# schematic2.net
KiCad netlist of a schematic drawn in EAGLE
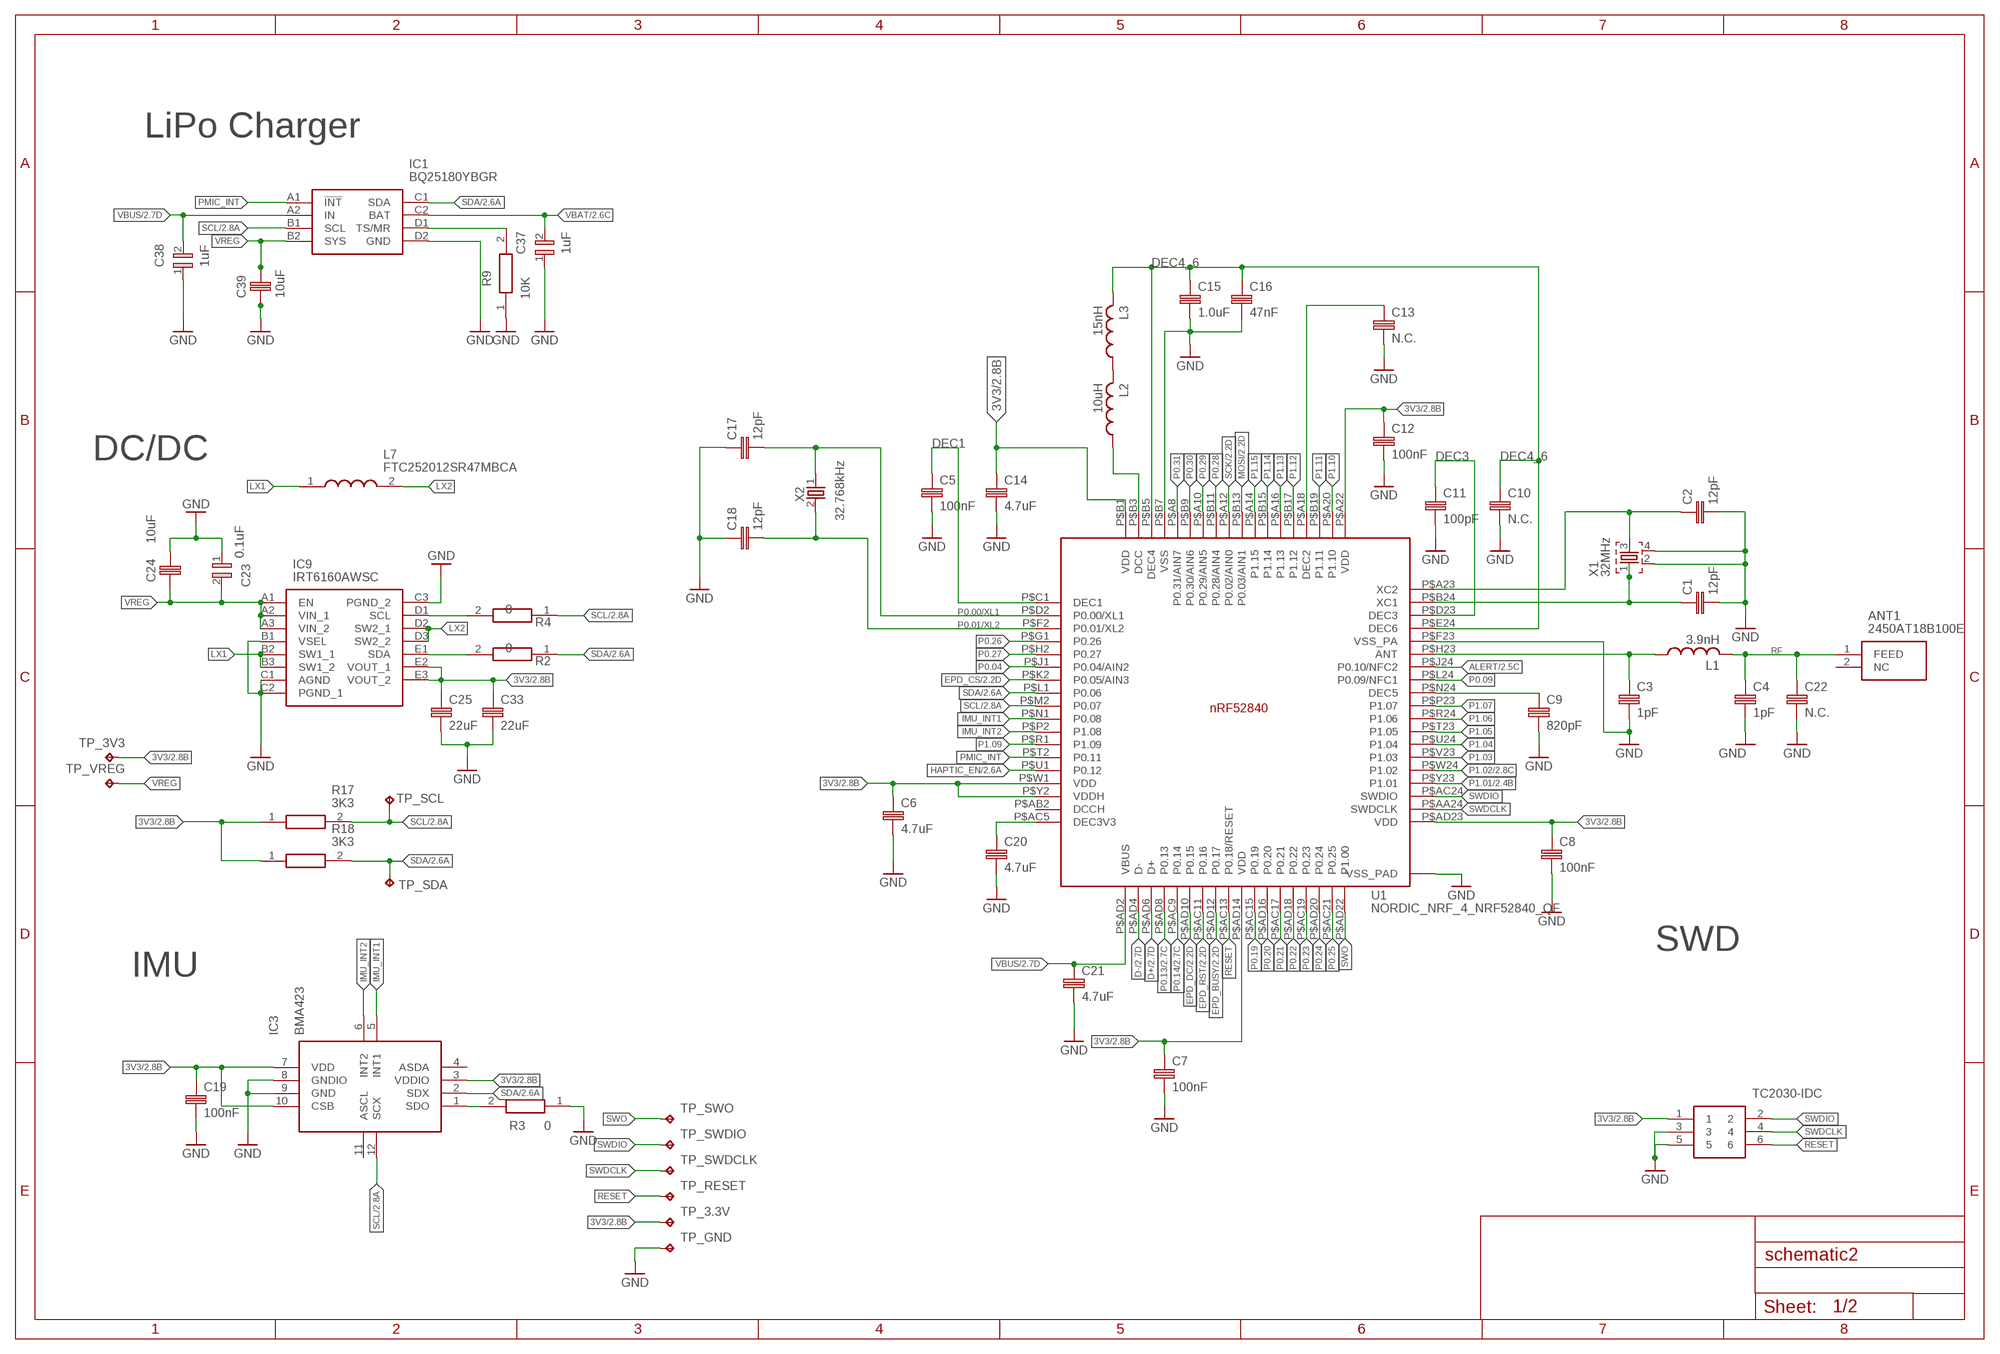
[diagram p0: schematic, sheet 1]
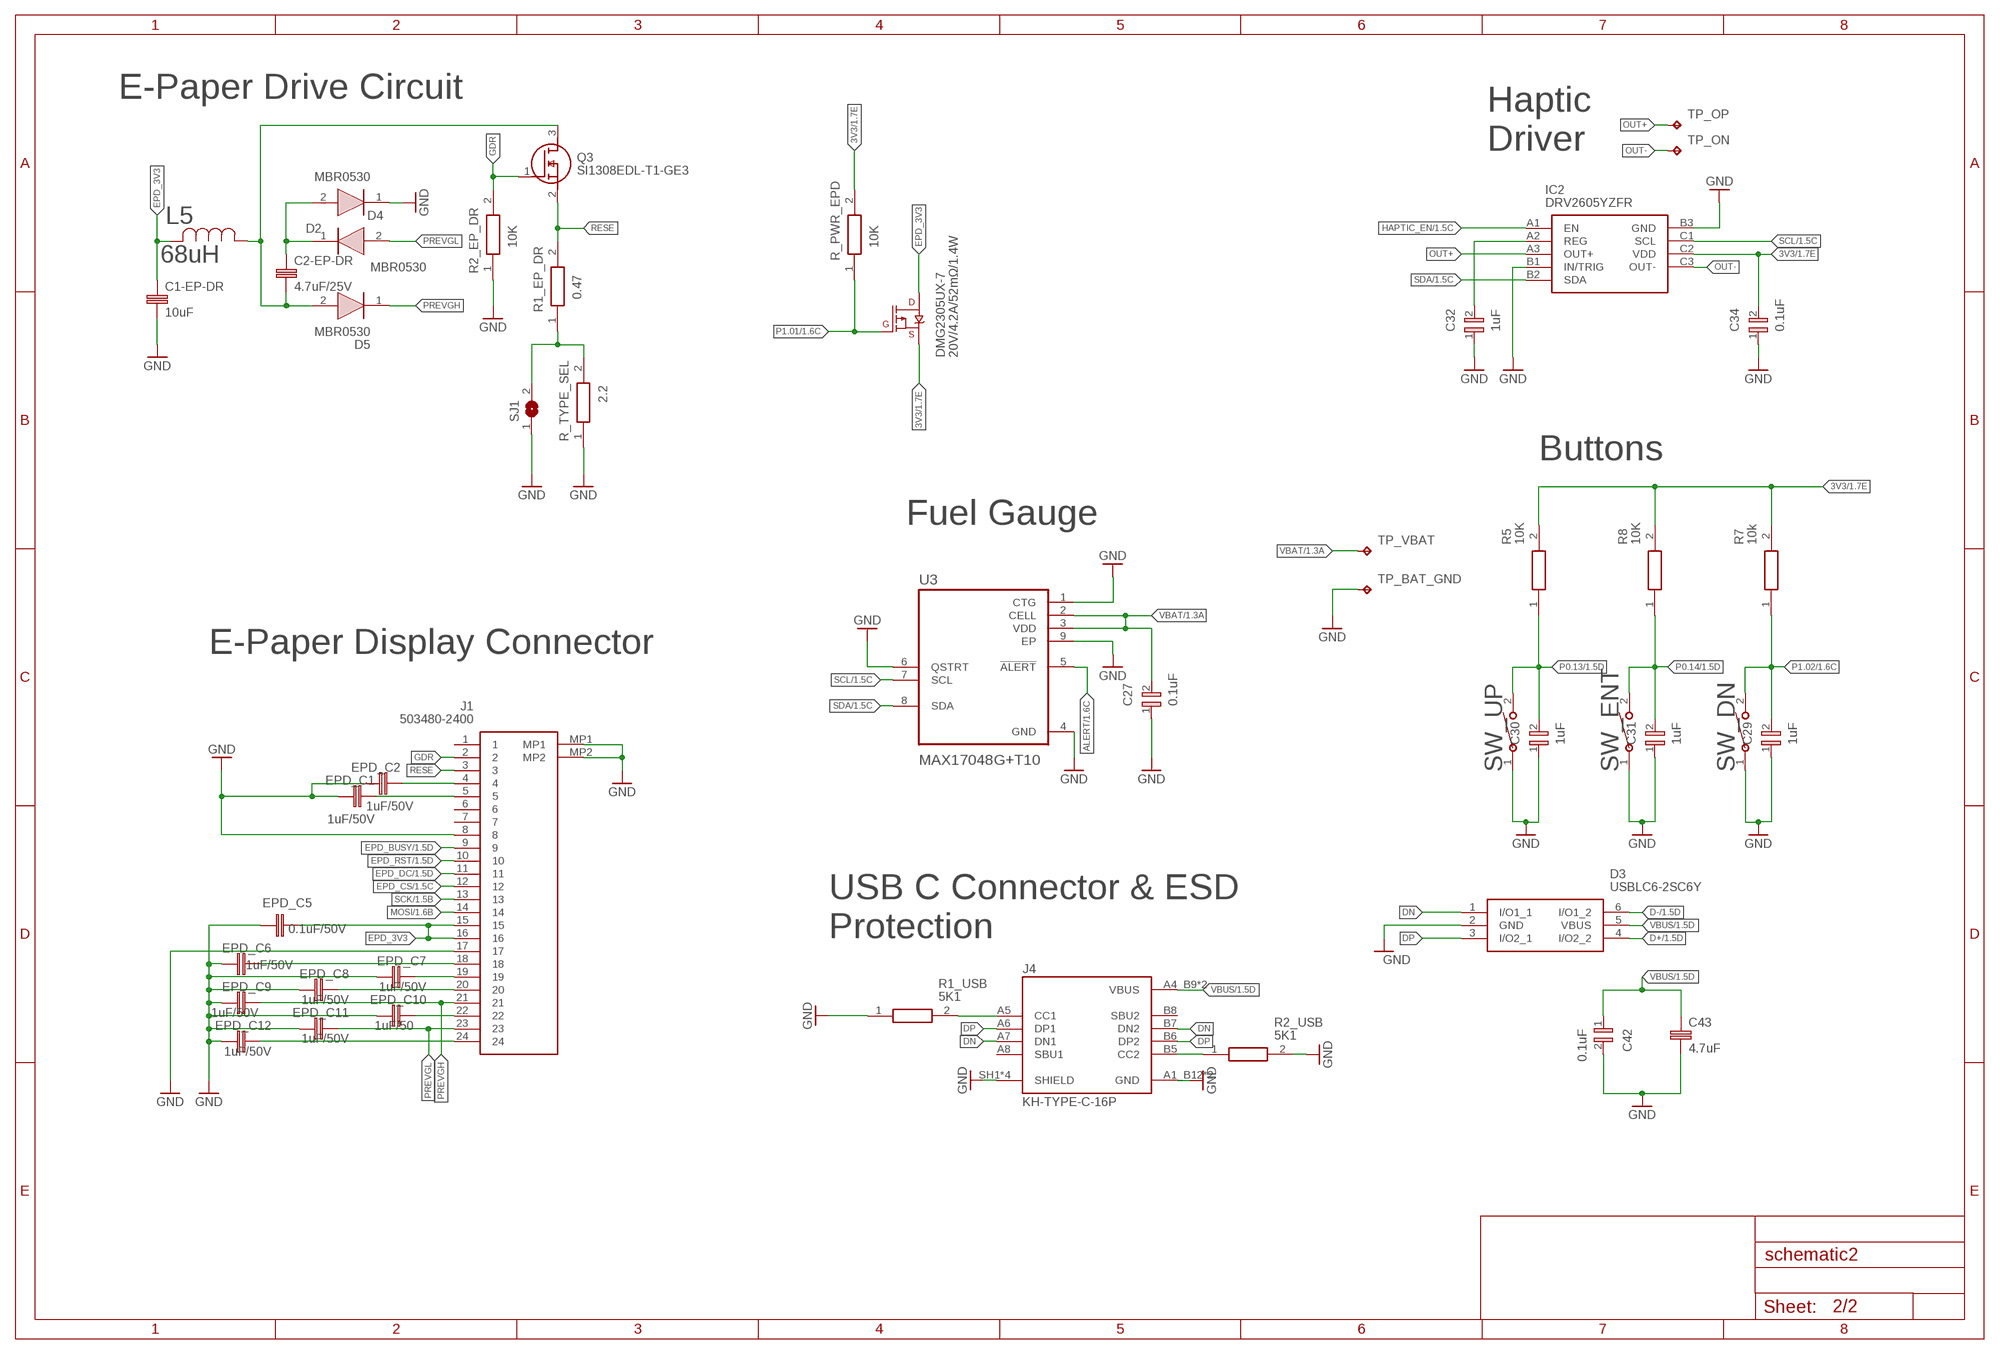
[diagram p1: schematic, sheet 2]

(export (version "E")
  (design (tool "Eeschema 10.0.6"))
  (components
    (comp (ref "ANT1")
      (value "2450AT18B100E")
      (footprint "eagle-import:2450AT18B100E_ANTC3216X140N")
      (fields (field (name "MOUSER_PART_NUMBER") "609-2450AT18B100E"))
      (libsource (lib "eagle-import") (part "2450AT18B100E_2450AT18B100E"))
    )
    (comp (ref "C1")
      (value "12pF")
      (footprint "eagle-import:NORDIC_NRF_3_RESC0201_L")
      (libsource (lib "eagle-import") (part "NORDIC_NRF_3_CAPACITOR_0201_L"))
    )
    (comp (ref "C2")
      (value "12pF")
      (footprint "eagle-import:NORDIC_NRF_3_RESC0201_L")
      (libsource (lib "eagle-import") (part "NORDIC_NRF_3_CAPACITOR_0201_L"))
    )
    (comp (ref "C3")
      (value "1pF")
      (footprint "eagle-import:NORDIC_NRF_3_RESC0201_L")
      (libsource (lib "eagle-import") (part "NORDIC_NRF_3_CAPACITOR_0201_L"))
    )
    (comp (ref "C4")
      (value "1pF")
      (footprint "eagle-import:NORDIC_NRF_3_RESC0201_L")
      (libsource (lib "eagle-import") (part "NORDIC_NRF_3_CAPACITOR_0201_L"))
    )
    (comp (ref "C5")
      (value "100nF")
      (footprint "eagle-import:NORDIC_NRF_3_RESC0201_L")
      (libsource (lib "eagle-import") (part "NORDIC_NRF_3_CAPACITOR_0201_L"))
    )
    (comp (ref "C6")
      (value "4.7uF")
      (footprint "eagle-import:NORDIC_NRF_3_RESC0402_L")
      (libsource (lib "eagle-import") (part "NORDIC_NRF_3_CAPACITOR_0402_L"))
    )
    (comp (ref "C7")
      (value "100nF")
      (footprint "eagle-import:NORDIC_NRF_3_RESC0201_L")
      (libsource (lib "eagle-import") (part "NORDIC_NRF_3_CAPACITOR_0201_L"))
    )
    (comp (ref "C8")
      (value "100nF")
      (footprint "eagle-import:NORDIC_NRF_3_RESC0201_L")
      (libsource (lib "eagle-import") (part "NORDIC_NRF_3_CAPACITOR_0201_L"))
    )
    (comp (ref "C9")
      (value "820pF")
      (footprint "eagle-import:NORDIC_NRF_3_RESC0201_L")
      (libsource (lib "eagle-import") (part "NORDIC_NRF_3_CAPACITOR_0201_L"))
    )
    (comp (ref "C10")
      (value "N.C.")
      (footprint "eagle-import:NORDIC_NRF_3_RESC0201_L")
      (libsource (lib "eagle-import") (part "NORDIC_NRF_3_CAPACITOR_0201_L"))
    )
    (comp (ref "C11")
      (value "100pF")
      (footprint "eagle-import:NORDIC_NRF_3_RESC0201_L")
      (libsource (lib "eagle-import") (part "NORDIC_NRF_3_CAPACITOR_0201_L"))
    )
    (comp (ref "C12")
      (value "100nF")
      (footprint "eagle-import:NORDIC_NRF_3_RESC0201_L")
      (libsource (lib "eagle-import") (part "NORDIC_NRF_3_CAPACITOR_0201_L"))
    )
    (comp (ref "C13")
      (value "N.C.")
      (footprint "eagle-import:NORDIC_NRF_3_RESC0201_L")
      (libsource (lib "eagle-import") (part "NORDIC_NRF_3_CAPACITOR_0201_L"))
    )
    (comp (ref "C14")
      (value "4.7uF")
      (footprint "eagle-import:NORDIC_NRF_3_RESC0402_L")
      (libsource (lib "eagle-import") (part "NORDIC_NRF_3_CAPACITOR_0402_L"))
    )
    (comp (ref "C15")
      (value "1.0uF")
      (footprint "eagle-import:NORDIC_NRF_3_RESC0402_L")
      (libsource (lib "eagle-import") (part "NORDIC_NRF_3_CAPACITOR_0402_L"))
    )
    (comp (ref "C16")
      (value "47nF")
      (footprint "eagle-import:NORDIC_NRF_3_RESC0201_L")
      (libsource (lib "eagle-import") (part "NORDIC_NRF_3_CAPACITOR_0201_L"))
    )
    (comp (ref "C17")
      (value "12pF")
      (footprint "eagle-import:NORDIC_NRF_3_RESC0201_L")
      (libsource (lib "eagle-import") (part "NORDIC_NRF_3_CAPACITOR_0201_L"))
    )
    (comp (ref "C18")
      (value "12pF")
      (footprint "eagle-import:NORDIC_NRF_3_RESC0201_L")
      (libsource (lib "eagle-import") (part "NORDIC_NRF_3_CAPACITOR_0201_L"))
    )
    (comp (ref "C19")
      (value "100nF")
      (footprint "eagle-import:NORDIC_NRF_3_RESC0201_L")
      (libsource (lib "eagle-import") (part "NORDIC_NRF_3_CAPACITOR_0201_L"))
    )
    (comp (ref "C20")
      (value "4.7uF")
      (footprint "eagle-import:NORDIC_NRF_3_RESC0402_L")
      (libsource (lib "eagle-import") (part "NORDIC_NRF_3_CAPACITOR_0402_L"))
    )
    (comp (ref "C21")
      (value "4.7uF")
      (footprint "eagle-import:NORDIC_NRF_3_RESC0402_L")
      (libsource (lib "eagle-import") (part "NORDIC_NRF_3_CAPACITOR_0402_L"))
    )
    (comp (ref "C22")
      (value "N.C.")
      (footprint "eagle-import:NORDIC_NRF_3_RESC0201_L")
      (libsource (lib "eagle-import") (part "NORDIC_NRF_3_CAPACITOR_0201_L"))
    )
    (comp (ref "C23")
      (value "0.1uF")
      (footprint "eagle-import:GRM011R60J152KE01L_2_CAPC0201X13N")
      (fields (field (name "MF") "Murata") (field (name "MP") "GRM011R60J152KE01L"))
      (libsource (lib "eagle-import") (part "GRM011R60J152KE01L_2_GRM011R60J152KE01L"))
    )
    (comp (ref "C24")
      (value "10uF")
      (footprint "eagle-import:NORDIC_NRF_3_RESC0402_L")
      (libsource (lib "eagle-import") (part "NORDIC_NRF_3_CAPACITOR_0402_L"))
    )
    (comp (ref "C25")
      (value "22uF")
      (footprint "eagle-import:NORDIC_NRF_3_RESC0402_L")
      (libsource (lib "eagle-import") (part "NORDIC_NRF_3_CAPACITOR_0402_L"))
    )
    (comp (ref "C33")
      (value "22uF")
      (footprint "eagle-import:NORDIC_NRF_3_RESC0402_L")
      (libsource (lib "eagle-import") (part "NORDIC_NRF_3_CAPACITOR_0402_L"))
    )
    (comp (ref "C37")
      (value "1uF")
      (footprint "eagle-import:GRM011R60J152KE01L_2_CAPC0201X13N")
      (fields (field (name "MF") "Murata") (field (name "MP") "GRM011R60J152KE01L"))
      (libsource (lib "eagle-import") (part "GRM011R60J152KE01L_2_GRM011R60J152KE01L"))
    )
    (comp (ref "C38")
      (value "1uF")
      (footprint "eagle-import:GRM011R60J152KE01L_2_CAPC0201X13N")
      (fields (field (name "MF") "Murata") (field (name "MP") "GRM011R60J152KE01L"))
      (libsource (lib "eagle-import") (part "GRM011R60J152KE01L_2_GRM011R60J152KE01L"))
    )
    (comp (ref "C39")
      (value "10uF")
      (footprint "eagle-import:NORDIC_NRF_3_RESC0402_L")
      (libsource (lib "eagle-import") (part "NORDIC_NRF_3_CAPACITOR_0402_L"))
    )
    (comp (ref "IC1")
      (value "BQ25180YBGR")
      (footprint "eagle-import:BQ25180YBGR_BGA8C40P2X4_100X155X50")
      (fields (field (name "MOUSER_PART_NUMBER") "595-BQ25180YBGR"))
      (libsource (lib "eagle-import") (part "BQ25180YBGR_BQ25180YBGR"))
    )
    (comp (ref "IC3")
      (value "BMA423")
      (footprint "eagle-import:BMA423_BMA423")
      (fields (field (name "MOUSER_PART_NUMBER") "262-BMA423"))
      (libsource (lib "eagle-import") (part "BMA423_BMA423"))
    )
    (comp (ref "IC9")
      (value "IRT6160AWSC")
      (footprint "eagle-import:RT6160AWSC_BGA15C40P3X5_140X230X60")
      (fields
        (field (name "MANUFACTURER_PART_NUMBER") "RT6160AWSC")
        (field (name "MOUSER_PART_NUMBER") "835-RT6160AWSC")
      )
      (libsource (lib "eagle-import") (part "RT6160AWSC_RT6160AWSC"))
    )
    (comp (ref "J2")
      (value "TC2030-IDC")
      (footprint "eagle-import:TC2030-IDC_TC2030IDC")
      (libsource (lib "eagle-import") (part "TC2030-IDC_TC2030-IDC"))
    )
    (comp (ref "L1")
      (value "3.9nH")
      (footprint "eagle-import:NORDIC_NRF_2_RESC0402_L")
      (libsource (lib "eagle-import") (part "NORDIC_NRF_2_INDUCTOR_0402_L"))
    )
    (comp (ref "L2")
      (value "10uH")
      (footprint "eagle-import:NORDIC_NRF_2_RESC0402_L")
      (libsource (lib "eagle-import") (part "NORDIC_NRF_2_INDUCTOR_0402_L"))
    )
    (comp (ref "L3")
      (value "15nH")
      (footprint "eagle-import:NORDIC_NRF_2_RESC0402_L")
      (libsource (lib "eagle-import") (part "NORDIC_NRF_2_INDUCTOR_0402_L"))
    )
    (comp (ref "L7")
      (value "FTC252012SR47MBCA")
      (footprint "eagle-import:MLP2016SR47MT0S1_INDC2016X100N")
      (libsource (lib "eagle-import") (part "MLP2016SR47MT0S1_FTC252012SR47MBCA"))
    )
    (comp (ref "R2")
      (value "0")
      (footprint "eagle-import:ERA-1AEB3401C_0201")
      (libsource (lib "eagle-import") (part "ERA-1AEB3401C_CPF0201D7K68C1"))
    )
    (comp (ref "R3")
      (value "0")
      (footprint "eagle-import:CPF0201D7K68C1_0201")
      (libsource (lib "eagle-import") (part "CPF0201D7K68C1_CPF0201D7K68C1"))
    )
    (comp (ref "R4")
      (value "0")
      (footprint "eagle-import:ERA-1AEB3401C_0201")
      (libsource (lib "eagle-import") (part "ERA-1AEB3401C_CPF0201D7K68C1"))
    )
    (comp (ref "R9")
      (value "10K")
      (footprint "eagle-import:ERA-1AEB3401C_0201")
      (libsource (lib "eagle-import") (part "ERA-1AEB3401C_CPF0201D7K68C1"))
    )
    (comp (ref "R17")
      (value "3K3")
      (footprint "eagle-import:CPF0201D7K68C1_0201")
      (libsource (lib "eagle-import") (part "CPF0201D7K68C1_CPF0201D7K68C1"))
    )
    (comp (ref "R18")
      (value "3K3")
      (footprint "eagle-import:CPF0201D7K68C1_0201")
      (libsource (lib "eagle-import") (part "CPF0201D7K68C1_CPF0201D7K68C1"))
    )
    (comp (ref "TP_3.3V")
      (value "HECTOR_WATCH_1_TPTP20R")
      (footprint "eagle-import:HECTOR_WATCH_1_TP20R")
      (libsource (lib "eagle-import") (part "HECTOR_WATCH_1_TPTP20R"))
    )
    (comp (ref "TP_3V3")
      (value "HECTOR_WATCH_1_TPTP20R")
      (footprint "eagle-import:HECTOR_WATCH_1_TP20R")
      (libsource (lib "eagle-import") (part "HECTOR_WATCH_1_TPTP20R"))
    )
    (comp (ref "TP_GND")
      (value "HECTOR_WATCH_1_TPTP20R")
      (footprint "eagle-import:HECTOR_WATCH_1_TP20R")
      (libsource (lib "eagle-import") (part "HECTOR_WATCH_1_TPTP20R"))
    )
    (comp (ref "TP_RESET")
      (value "HECTOR_WATCH_1_TPTP20R")
      (footprint "eagle-import:HECTOR_WATCH_1_TP20R")
      (libsource (lib "eagle-import") (part "HECTOR_WATCH_1_TPTP20R"))
    )
    (comp (ref "TP_SCL")
      (value "HECTOR_WATCH_1_TPTP20R")
      (footprint "eagle-import:HECTOR_WATCH_1_TP20R")
      (libsource (lib "eagle-import") (part "HECTOR_WATCH_1_TPTP20R"))
    )
    (comp (ref "TP_SDA")
      (value "HECTOR_WATCH_1_TPTP20R")
      (footprint "eagle-import:HECTOR_WATCH_1_TP20R")
      (libsource (lib "eagle-import") (part "HECTOR_WATCH_1_TPTP20R"))
    )
    (comp (ref "TP_SWDCLK")
      (value "HECTOR_WATCH_1_TPTP20R")
      (footprint "eagle-import:HECTOR_WATCH_1_TP20R")
      (libsource (lib "eagle-import") (part "HECTOR_WATCH_1_TPTP20R"))
    )
    (comp (ref "TP_SWDIO")
      (value "HECTOR_WATCH_1_TPTP20R")
      (footprint "eagle-import:HECTOR_WATCH_1_TP20R")
      (libsource (lib "eagle-import") (part "HECTOR_WATCH_1_TPTP20R"))
    )
    (comp (ref "TP_SWO")
      (value "HECTOR_WATCH_1_TPTP20R")
      (footprint "eagle-import:HECTOR_WATCH_1_TP20R")
      (libsource (lib "eagle-import") (part "HECTOR_WATCH_1_TPTP20R"))
    )
    (comp (ref "TP_VREG")
      (value "HECTOR_WATCH_1_TPTP20R")
      (footprint "eagle-import:HECTOR_WATCH_1_TP20R")
      (libsource (lib "eagle-import") (part "HECTOR_WATCH_1_TPTP20R"))
    )
    (comp (ref "U$3")
      (value "NORDIC_NRF_3_CAPACITOR_0402_L")
      (footprint "eagle-import:NORDIC_NRF_3_RESC0402_L")
      (libsource (lib "eagle-import") (part "NORDIC_NRF_3_CAPACITOR_0402_L"))
    )
    (comp (ref "U1")
      (value "NORDIC_NRF_4_NRF52840_QF")
      (footprint "eagle-import:NORDIC_NRF_4_AQFN50P700X700X85_HS-74N")
      (libsource (lib "eagle-import") (part "NORDIC_NRF_4_NRF52840_QF"))
    )
    (comp (ref "X1")
      (value "32MHz")
      (footprint "eagle-import:NORDIC_NRF_BT-XTAL_2016_N")
      (libsource (lib "eagle-import") (part "NORDIC_NRF_XTAL_32MHZ"))
    )
    (comp (ref "X2")
      (value "32.768kHz")
      (footprint "eagle-import:NORDIC_NRF_1_XTAL_3215_N")
      (libsource (lib "eagle-import") (part "NORDIC_NRF_1_XTAL_32KHZ"))
    )
    (comp (ref "C1-EP-DR")
      (value "10uF")
      (footprint "eagle-import:NORDIC_NRF_3_RESC0402_L")
      (libsource (lib "eagle-import") (part "NORDIC_NRF_3_CAPACITOR_0402_L"))
    )
    (comp (ref "C2-EP-DR")
      (value "4.7uF/25V")
      (footprint "eagle-import:NORDIC_NRF_3_RESC0402_L")
      (libsource (lib "eagle-import") (part "NORDIC_NRF_3_CAPACITOR_0402_L"))
    )
    (comp (ref "C27")
      (value "0.1uF")
      (footprint "eagle-import:GRM011R60J152KE01L_2_CAPC0201X13N")
      (fields (field (name "MF") "Murata") (field (name "MP") "GRM011R60J152KE01L"))
      (libsource (lib "eagle-import") (part "GRM011R60J152KE01L_2_GRM011R60J152KE01L"))
    )
    (comp (ref "C29")
      (value "1uF")
      (footprint "eagle-import:GRM011R60J152KE01L_2_CAPC0201X13N")
      (fields (field (name "MF") "Murata") (field (name "MP") "GRM011R60J152KE01L"))
      (libsource (lib "eagle-import") (part "GRM011R60J152KE01L_2_GRM011R60J152KE01L"))
    )
    (comp (ref "C30")
      (value "1uF")
      (footprint "eagle-import:GRM011R60J152KE01L_2_CAPC0201X13N")
      (fields (field (name "MF") "Murata") (field (name "MP") "GRM011R60J152KE01L"))
      (libsource (lib "eagle-import") (part "GRM011R60J152KE01L_2_GRM011R60J152KE01L"))
    )
    (comp (ref "C31")
      (value "1uF")
      (footprint "eagle-import:GRM011R60J152KE01L_2_CAPC0201X13N")
      (fields (field (name "MF") "Murata") (field (name "MP") "GRM011R60J152KE01L"))
      (libsource (lib "eagle-import") (part "GRM011R60J152KE01L_2_GRM011R60J152KE01L"))
    )
    (comp (ref "C32")
      (value "1uF")
      (footprint "eagle-import:GRM011R60J152KE01L_2_CAPC0201X13N")
      (fields (field (name "MF") "Murata") (field (name "MP") "GRM011R60J152KE01L"))
      (libsource (lib "eagle-import") (part "GRM011R60J152KE01L_2_GRM011R60J152KE01L"))
    )
    (comp (ref "C34")
      (value "0.1uF")
      (footprint "eagle-import:GRM011R60J152KE01L_2_CAPC0201X13N")
      (fields (field (name "MF") "Murata") (field (name "MP") "GRM011R60J152KE01L"))
      (libsource (lib "eagle-import") (part "GRM011R60J152KE01L_2_GRM011R60J152KE01L"))
    )
    (comp (ref "C42")
      (value "0.1uF")
      (footprint "eagle-import:GRM011R60J152KE01L_2_CAPC0201X13N")
      (fields (field (name "MF") "Murata") (field (name "MP") "GRM011R60J152KE01L"))
      (libsource (lib "eagle-import") (part "GRM011R60J152KE01L_2_GRM011R60J152KE01L"))
    )
    (comp (ref "C43")
      (value "4.7uF")
      (footprint "eagle-import:NORDIC_NRF_3_RESC0402_L")
      (libsource (lib "eagle-import") (part "NORDIC_NRF_3_CAPACITOR_0402_L"))
    )
    (comp (ref "D2")
      (value "MBR0530")
      (footprint "eagle-import:ESP32_C6_LIBRARY_5_SOD3716X135N")
      (fields (field (name "MF") "ON Semiconductor"))
      (libsource (lib "eagle-import") (part "ESP32_C6_LIBRARY_5_MBR0530"))
    )
    (comp (ref "D3")
      (value "USBLC6-2SC6Y")
      (footprint "eagle-import:ESP32_C6_LIBRARY_3_SOT95P280X145-6N")
      (fields (field (name "MF") "STMicroelectronics"))
      (libsource (lib "eagle-import") (part "ESP32_C6_LIBRARY_3_USBLC6-2SC6Y"))
    )
    (comp (ref "D4")
      (value "MBR0530")
      (footprint "eagle-import:ESP32_C6_LIBRARY_5_SOD3716X135N")
      (fields (field (name "MF") "ON Semiconductor"))
      (libsource (lib "eagle-import") (part "ESP32_C6_LIBRARY_5_MBR0530"))
    )
    (comp (ref "D5")
      (value "MBR0530")
      (footprint "eagle-import:ESP32_C6_LIBRARY_5_SOD3716X135N")
      (fields (field (name "MF") "ON Semiconductor"))
      (libsource (lib "eagle-import") (part "ESP32_C6_LIBRARY_5_MBR0530"))
    )
    (comp (ref "DMG2305UX-7")
      (value "20V/4.2A/52mΩ/1.4W")
      (footprint "eagle-import:ESP32_C6_LIBRARY_4_ESP32_C6_LIBRARY_4_ESP32_C6_LIBRARY_4_ESP32_C6_LIBRARY_4_ESP32_WROVER_SPARKFUN-DISCRETESEMI_SOT23-3")
      (libsource (lib "eagle-import") (part "ESP32_C6_LIBRARY_4_ESP32_WROVER_SPARKFUN-DISCRETESEMI_MOSFET_PCH-DMG2305UX-7"))
    )
    (comp (ref "EPD_C1")
      (value "1uF/50V")
      (footprint "eagle-import:NORDIC_NRF_3_RESC0402_L")
      (libsource (lib "eagle-import") (part "NORDIC_NRF_3_CAPACITOR_0402_L"))
    )
    (comp (ref "EPD_C2")
      (value "1uF/50V")
      (footprint "eagle-import:NORDIC_NRF_3_RESC0402_L")
      (libsource (lib "eagle-import") (part "NORDIC_NRF_3_CAPACITOR_0402_L"))
    )
    (comp (ref "EPD_C5")
      (value "0.1uF/50V")
      (footprint "eagle-import:NORDIC_NRF_3_RESC0201_L")
      (libsource (lib "eagle-import") (part "NORDIC_NRF_3_CAPACITOR_0201_L"))
    )
    (comp (ref "EPD_C6")
      (value "1uF/50V")
      (footprint "eagle-import:NORDIC_NRF_3_RESC0402_L")
      (libsource (lib "eagle-import") (part "NORDIC_NRF_3_CAPACITOR_0402_L"))
    )
    (comp (ref "EPD_C7")
      (value "1uF/50V")
      (footprint "eagle-import:NORDIC_NRF_3_RESC0402_L")
      (libsource (lib "eagle-import") (part "NORDIC_NRF_3_CAPACITOR_0402_L"))
    )
    (comp (ref "EPD_C8")
      (value "1uF/50V")
      (footprint "eagle-import:NORDIC_NRF_3_RESC0402_L")
      (libsource (lib "eagle-import") (part "NORDIC_NRF_3_CAPACITOR_0402_L"))
    )
    (comp (ref "EPD_C9")
      (value "1uF/50V")
      (footprint "eagle-import:NORDIC_NRF_3_RESC0402_L")
      (libsource (lib "eagle-import") (part "NORDIC_NRF_3_CAPACITOR_0402_L"))
    )
    (comp (ref "EPD_C10")
      (value "1uF/50")
      (footprint "eagle-import:NORDIC_NRF_3_RESC0402_L")
      (libsource (lib "eagle-import") (part "NORDIC_NRF_3_CAPACITOR_0402_L"))
    )
    (comp (ref "EPD_C11")
      (value "1uF/50V")
      (footprint "eagle-import:NORDIC_NRF_3_RESC0402_L")
      (libsource (lib "eagle-import") (part "NORDIC_NRF_3_CAPACITOR_0402_L"))
    )
    (comp (ref "EPD_C12")
      (value "1uF/50V")
      (footprint "eagle-import:NORDIC_NRF_3_RESC0402_L")
      (libsource (lib "eagle-import") (part "NORDIC_NRF_3_CAPACITOR_0402_L"))
    )
    (comp (ref "IC2")
      (value "DRV2605YZFR")
      (footprint "eagle-import:DRV2605YZFR_BGA9C50P3X3_144X144X62")
      (libsource (lib "eagle-import") (part "DRV2605YZFR_DRV2605YZFR"))
    )
    (comp (ref "J1")
      (value "503480-2400")
      (footprint "eagle-import:503480-2400_5034802400")
      (fields (field (name "MOUSER_PART_NUMBER") "538-503480-2400"))
      (libsource (lib "eagle-import") (part "503480-2400_503480-2400"))
    )
    (comp (ref "J4")
      (value "KH-TYPE-C-16P")
      (footprint "eagle-import:KH-TYPE-C-16P_KINGHELM_KH-TYPE-C-16P")
      (fields (field (name "MF") "kinghelm"))
      (libsource (lib "eagle-import") (part "KH-TYPE-C-16P_KH-TYPE-C-16P"))
    )
    (comp (ref "L5")
      (value "68uH")
      (footprint "eagle-import:ESP32_C6_LIBRARY_2_IND_4828-WE-TPC_WRE")
      (fields
        (field (name "MANUFACTURER_PART_NUMBER") "744043680")
        (field (name "COPYRIGHT") "Copyright (C) 2024 Ultra Librarian. All rights reserved.")
      )
      (libsource (lib "eagle-import") (part "ESP32_C6_LIBRARY_2_744043680IND_4828-WE-TPC_WRE"))
    )
    (comp (ref "Q3")
      (value "SI1308EDL-T1-GE3")
      (footprint "eagle-import:ESP32_C6_LIBRARY_6_SOT65P210X110-3N")
      (fields (field (name "MF") "Vishay Siliconix"))
      (libsource (lib "eagle-import") (part "ESP32_C6_LIBRARY_6_SI1308EDL-T1-GE3"))
    )
    (comp (ref "R1_EP_DR")
      (value "0.47")
      (footprint "eagle-import:ERA-1AEB3401C_0201")
      (libsource (lib "eagle-import") (part "ERA-1AEB3401C_CPF0201D7K68C1"))
    )
    (comp (ref "R1_USB")
      (value "5K1")
      (footprint "eagle-import:ERA-1AEB3401C_0201")
      (libsource (lib "eagle-import") (part "ERA-1AEB3401C_CPF0201D7K68C1"))
    )
    (comp (ref "R2_EP_DR")
      (value "10K")
      (footprint "eagle-import:ERA-1AEB3401C_0201")
      (libsource (lib "eagle-import") (part "ERA-1AEB3401C_CPF0201D7K68C1"))
    )
    (comp (ref "R2_USB")
      (value "5K1")
      (footprint "eagle-import:ERA-1AEB3401C_0201")
      (libsource (lib "eagle-import") (part "ERA-1AEB3401C_CPF0201D7K68C1"))
    )
    (comp (ref "R5")
      (value "10K")
      (footprint "eagle-import:ERA-1AEB3401C_0201")
      (libsource (lib "eagle-import") (part "ERA-1AEB3401C_CPF0201D7K68C1"))
    )
    (comp (ref "R7")
      (value "10k")
      (footprint "eagle-import:ERA-1AEB3401C_0201")
      (libsource (lib "eagle-import") (part "ERA-1AEB3401C_CPF0201D7K68C1"))
    )
    (comp (ref "R8")
      (value "10K")
      (footprint "eagle-import:ERA-1AEB3401C_0201")
      (libsource (lib "eagle-import") (part "ERA-1AEB3401C_CPF0201D7K68C1"))
    )
    (comp (ref "R_PWR_EPD")
      (value "10K")
      (footprint "eagle-import:ERA-1AEB3401C_0201")
      (libsource (lib "eagle-import") (part "ERA-1AEB3401C_CPF0201D7K68C1"))
    )
    (comp (ref "R_TYPE_SEL")
      (value "2.2")
      (footprint "eagle-import:ERA-1AEB3401C_0201")
      (libsource (lib "eagle-import") (part "ERA-1AEB3401C_CPF0201D7K68C1"))
    )
    (comp (ref "SJ1")
      (value "ESP32_C6_LIBRARY_7_JUMPER_SJ")
      (footprint "eagle-import:ESP32_C6_LIBRARY_7_JUMPER_SJ")
      (libsource (lib "eagle-import") (part "ESP32_C6_LIBRARY_7_JUMPER_SJ"))
    )
    (comp (ref "SW_DN")
      (value "2025-10-22_07-23-44_LIBRARY_EVP-AKE31ASW_EVP-AKE31A_PAN")
      (footprint "eagle-import:2025-10-22_07-23-44_LIBRARY_SW_EVP-AKE31A_PAN")
      (fields
        (field (name "MANUFACTURER_PART_NUMBER") "EVP-AKE31A")
        (field (name "COPYRIGHT") "Copyright (C) 2025 Ultra Librarian. All rights reserved.")
      )
      (libsource (lib "eagle-import") (part "2025-10-22_07-23-44_LIBRARY_EVP-AKE31ASW_EVP-AKE31A_PAN"))
    )
    (comp (ref "SW_ENT")
      (value "2025-10-22_07-23-44_LIBRARY_EVP-AKE31ASW_EVP-AKE31A_PAN")
      (footprint "eagle-import:2025-10-22_07-23-44_LIBRARY_SW_EVP-AKE31A_PAN")
      (fields
        (field (name "MANUFACTURER_PART_NUMBER") "EVP-AKE31A")
        (field (name "COPYRIGHT") "Copyright (C) 2025 Ultra Librarian. All rights reserved.")
      )
      (libsource (lib "eagle-import") (part "2025-10-22_07-23-44_LIBRARY_EVP-AKE31ASW_EVP-AKE31A_PAN"))
    )
    (comp (ref "SW_UP")
      (value "2025-10-22_07-23-44_LIBRARY_EVP-AKE31ASW_EVP-AKE31A_PAN")
      (footprint "eagle-import:2025-10-22_07-23-44_LIBRARY_SW_EVP-AKE31A_PAN")
      (fields
        (field (name "MANUFACTURER_PART_NUMBER") "EVP-AKE31A")
        (field (name "COPYRIGHT") "Copyright (C) 2025 Ultra Librarian. All rights reserved.")
      )
      (libsource (lib "eagle-import") (part "2025-10-22_07-23-44_LIBRARY_EVP-AKE31ASW_EVP-AKE31A_PAN"))
    )
    (comp (ref "TP_BAT_GND")
      (value "HECTOR_WATCH_1_TPTP20R")
      (footprint "eagle-import:HECTOR_WATCH_1_TP20R")
      (libsource (lib "eagle-import") (part "HECTOR_WATCH_1_TPTP20R"))
    )
    (comp (ref "TP_ON")
      (value "HECTOR_WATCH_1_TPTP20R")
      (footprint "eagle-import:HECTOR_WATCH_1_TP20R")
      (libsource (lib "eagle-import") (part "HECTOR_WATCH_1_TPTP20R"))
    )
    (comp (ref "TP_OP")
      (value "HECTOR_WATCH_1_TPTP20R")
      (footprint "eagle-import:HECTOR_WATCH_1_TP20R")
      (libsource (lib "eagle-import") (part "HECTOR_WATCH_1_TPTP20R"))
    )
    (comp (ref "TP_VBAT")
      (value "HECTOR_WATCH_1_TPTP20R")
      (footprint "eagle-import:HECTOR_WATCH_1_TP20R")
      (libsource (lib "eagle-import") (part "HECTOR_WATCH_1_TPTP20R"))
    )
    (comp (ref "U3")
      (value "MAX17048G+T10")
      (footprint "eagle-import:ESP32_C6_LIBRARY_SON50P200X200X80-9N")
      (fields (field (name "MF") "Analog Devices"))
      (libsource (lib "eagle-import") (part "ESP32_C6_LIBRARY_MAX17048G+T10"))
    )
  )
  (nets
    (net (code "1") (name "3V3") (class "Default")
      (node (ref "C12") (pin "1") (pinfunction "1_1") (pintype "passive"))
      (node (ref "C14") (pin "1") (pinfunction "1_1") (pintype "passive"))
      (node (ref "C19") (pin "1") (pinfunction "1_1") (pintype "passive"))
      (node (ref "C25") (pin "1") (pinfunction "1_1") (pintype "passive"))
      (node (ref "C33") (pin "1") (pinfunction "1_1") (pintype "passive"))
      (node (ref "C34") (pin "2") (pinfunction "2_2") (pintype "passive"))
      (node (ref "C6") (pin "1") (pinfunction "1_1") (pintype "passive"))
      (node (ref "C7") (pin "1") (pinfunction "1_1") (pintype "passive"))
      (node (ref "C8") (pin "1") (pinfunction "1_1") (pintype "passive"))
      (node (ref "DMG2305UX-7") (pin "2") (pinfunction "S_2") (pintype "bidirectional"))
      (node (ref "IC2") (pin "C2") (pinfunction "VDD_C2") (pintype "bidirectional"))
      (node (ref "IC3") (pin "10") (pinfunction "CSB_10") (pintype "bidirectional"))
      (node (ref "IC3") (pin "3") (pinfunction "VDDIO_3") (pintype "bidirectional"))
      (node (ref "IC3") (pin "7") (pinfunction "VDD_7") (pintype "bidirectional"))
      (node (ref "IC9") (pin "E2") (pinfunction "VOUT_1_E2") (pintype "bidirectional"))
      (node (ref "IC9") (pin "E3") (pinfunction "VOUT_2_E3") (pintype "bidirectional"))
      (node (ref "J2") (pin "1") (pinfunction "1_1") (pintype "bidirectional"))
      (node (ref "R17") (pin "1") (pinfunction "1_1") (pintype "bidirectional"))
      (node (ref "R18") (pin "1") (pinfunction "1_1") (pintype "bidirectional"))
      (node (ref "R5") (pin "2") (pinfunction "2_2") (pintype "bidirectional"))
      (node (ref "R7") (pin "2") (pinfunction "2_2") (pintype "bidirectional"))
      (node (ref "R8") (pin "2") (pinfunction "2_2") (pintype "bidirectional"))
      (node (ref "R_PWR_EPD") (pin "2") (pinfunction "2_2") (pintype "bidirectional"))
      (node (ref "TP_3.3V") (pin "TP") (pinfunction "TP_TP") (pintype "input"))
      (node (ref "TP_3V3") (pin "TP") (pinfunction "TP_TP") (pintype "input"))
      (node (ref "U1") (pin "P$A22") (pinfunction "VDD_P$A22") (pintype "power_in"))
      (node (ref "U1") (pin "P$AD14") (pinfunction "VDD_P$AD14") (pintype "power_in"))
      (node (ref "U1") (pin "P$AD23") (pinfunction "VDD_P$AD23") (pintype "power_in"))
      (node (ref "U1") (pin "P$B1") (pinfunction "VDD_P$B1") (pintype "power_in"))
      (node (ref "U1") (pin "P$W1") (pinfunction "VDD_P$W1") (pintype "power_in"))
      (node (ref "U1") (pin "P$Y2") (pinfunction "VDDH_P$Y2") (pintype "power_in"))
    )
    (net (code "2") (name "ALERT") (class "Default")
      (node (ref "U1") (pin "P$J24") (pinfunction "P0.10/NFC2_P$J24") (pintype "bidirectional"))
      (node (ref "U3") (pin "5") (pinfunction "~{ALERT}_5") (pintype "output"))
    )
    (net (code "3") (name "D+") (class "Default")
      (node (ref "D3") (pin "4") (pinfunction "I/O2_2_4") (pintype "bidirectional"))
      (node (ref "U1") (pin "P$AD6") (pinfunction "D+_P$AD6") (pintype "bidirectional"))
    )
    (net (code "4") (name "D-") (class "Default")
      (node (ref "D3") (pin "6") (pinfunction "I/O1_2_6") (pintype "bidirectional"))
      (node (ref "U1") (pin "P$AD4") (pinfunction "D-_P$AD4") (pintype "bidirectional"))
    )
    (net (code "5") (name "DEC1") (class "Default")
      (node (ref "C5") (pin "1") (pinfunction "1_1") (pintype "passive"))
      (node (ref "U1") (pin "P$C1") (pinfunction "DEC1_P$C1") (pintype "power_in"))
    )
    (net (code "6") (name "DEC3") (class "Default")
      (node (ref "C11") (pin "1") (pinfunction "1_1") (pintype "passive"))
      (node (ref "U1") (pin "P$D23") (pinfunction "DEC3_P$D23") (pintype "bidirectional"))
    )
    (net (code "7") (name "DEC4_6") (class "Default")
      (node (ref "C10") (pin "1") (pinfunction "1_1") (pintype "passive"))
      (node (ref "C15") (pin "1") (pinfunction "1_1") (pintype "passive"))
      (node (ref "C16") (pin "1") (pinfunction "1_1") (pintype "passive"))
      (node (ref "L3") (pin "2") (pinfunction "2_2") (pintype "passive"))
      (node (ref "U1") (pin "P$B5") (pinfunction "DEC4_P$B5") (pintype "power_in"))
      (node (ref "U1") (pin "P$E24") (pinfunction "DEC6_P$E24") (pintype "bidirectional"))
    )
    (net (code "8") (name "DN") (class "Default")
      (node (ref "D3") (pin "1") (pinfunction "I/O1_1_1") (pintype "bidirectional"))
      (node (ref "J4") (pin "A7") (pinfunction "DN1_A7") (pintype "bidirectional"))
      (node (ref "J4") (pin "B7") (pinfunction "DN2_B7") (pintype "bidirectional"))
    )
    (net (code "9") (name "DP") (class "Default")
      (node (ref "D3") (pin "3") (pinfunction "I/O2_1_3") (pintype "bidirectional"))
      (node (ref "J4") (pin "A6") (pinfunction "DP1_A6") (pintype "bidirectional"))
      (node (ref "J4") (pin "B6") (pinfunction "DP2_B6") (pintype "bidirectional"))
    )
    (net (code "10") (name "EPD_3V3") (class "Default")
      (node (ref "C1-EP-DR") (pin "1") (pinfunction "1_1") (pintype "passive"))
      (node (ref "DMG2305UX-7") (pin "3") (pinfunction "D_3") (pintype "bidirectional"))
      (node (ref "EPD_C5") (pin "1") (pinfunction "1_1") (pintype "passive"))
      (node (ref "J1") (pin "15") (pinfunction "15_15") (pintype "bidirectional"))
      (node (ref "J1") (pin "16") (pinfunction "16_16") (pintype "bidirectional"))
      (node (ref "L5") (pin "2") (pinfunction "2_2") (pintype "passive"))
    )
    (net (code "11") (name "EPD_BUSY") (class "Default")
      (node (ref "J1") (pin "9") (pinfunction "9_9") (pintype "bidirectional"))
      (node (ref "U1") (pin "P$AD12") (pinfunction "P0.17_P$AD12") (pintype "bidirectional"))
    )
    (net (code "12") (name "EPD_CS") (class "Default")
      (node (ref "J1") (pin "12") (pinfunction "12_12") (pintype "bidirectional"))
      (node (ref "U1") (pin "P$K2") (pinfunction "P0.05/AIN3_P$K2") (pintype "bidirectional"))
    )
    (net (code "13") (name "EPD_DC") (class "Default")
      (node (ref "J1") (pin "11") (pinfunction "11_11") (pintype "bidirectional"))
      (node (ref "U1") (pin "P$AD10") (pinfunction "P0.15_P$AD10") (pintype "bidirectional"))
    )
    (net (code "14") (name "EPD_RST") (class "Default")
      (node (ref "J1") (pin "10") (pinfunction "10_10") (pintype "bidirectional"))
      (node (ref "U1") (pin "P$AC11") (pinfunction "P0.16_P$AC11") (pintype "bidirectional"))
    )
    (net (code "15") (name "GDR") (class "Default")
      (node (ref "J1") (pin "2") (pinfunction "2_2") (pintype "bidirectional"))
      (node (ref "Q3") (pin "1") (pinfunction "G_1") (pintype "bidirectional"))
      (node (ref "R2_EP_DR") (pin "2") (pinfunction "2_2") (pintype "bidirectional"))
    )
    (net (code "16") (name "GND") (class "Default")
      (node (ref "C1") (pin "2") (pinfunction "2_2") (pintype "passive"))
      (node (ref "C1-EP-DR") (pin "2") (pinfunction "2_2") (pintype "passive"))
      (node (ref "C10") (pin "2") (pinfunction "2_2") (pintype "passive"))
      (node (ref "C11") (pin "2") (pinfunction "2_2") (pintype "passive"))
      (node (ref "C12") (pin "2") (pinfunction "2_2") (pintype "passive"))
      (node (ref "C13") (pin "2") (pinfunction "2_2") (pintype "passive"))
      (node (ref "C14") (pin "2") (pinfunction "2_2") (pintype "passive"))
      (node (ref "C15") (pin "2") (pinfunction "2_2") (pintype "passive"))
      (node (ref "C16") (pin "2") (pinfunction "2_2") (pintype "passive"))
      (node (ref "C17") (pin "1") (pinfunction "1_1") (pintype "passive"))
      (node (ref "C18") (pin "1") (pinfunction "1_1") (pintype "passive"))
      (node (ref "C19") (pin "2") (pinfunction "2_2") (pintype "passive"))
      (node (ref "C2") (pin "2") (pinfunction "2_2") (pintype "passive"))
      (node (ref "C20") (pin "2") (pinfunction "2_2") (pintype "passive"))
      (node (ref "C21") (pin "2") (pinfunction "2_2") (pintype "passive"))
      (node (ref "C22") (pin "2") (pinfunction "2_2") (pintype "passive"))
      (node (ref "C23") (pin "1") (pinfunction "1_1") (pintype "passive"))
      (node (ref "C24") (pin "1") (pinfunction "1_1") (pintype "passive"))
      (node (ref "C25") (pin "2") (pinfunction "2_2") (pintype "passive"))
      (node (ref "C27") (pin "1") (pinfunction "1_1") (pintype "passive"))
      (node (ref "C29") (pin "1") (pinfunction "1_1") (pintype "passive"))
      (node (ref "C3") (pin "2") (pinfunction "2_2") (pintype "passive"))
      (node (ref "C30") (pin "1") (pinfunction "1_1") (pintype "passive"))
      (node (ref "C31") (pin "1") (pinfunction "1_1") (pintype "passive"))
      (node (ref "C32") (pin "1") (pinfunction "1_1") (pintype "passive"))
      (node (ref "C33") (pin "2") (pinfunction "2_2") (pintype "passive"))
      (node (ref "C34") (pin "1") (pinfunction "1_1") (pintype "passive"))
      (node (ref "C37") (pin "1") (pinfunction "1_1") (pintype "passive"))
      (node (ref "C38") (pin "1") (pinfunction "1_1") (pintype "passive"))
      (node (ref "C39") (pin "2") (pinfunction "2_2") (pintype "passive"))
      (node (ref "C4") (pin "2") (pinfunction "2_2") (pintype "passive"))
      (node (ref "C42") (pin "2") (pinfunction "2_2") (pintype "passive"))
      (node (ref "C43") (pin "2") (pinfunction "2_2") (pintype "passive"))
      (node (ref "C5") (pin "2") (pinfunction "2_2") (pintype "passive"))
      (node (ref "C6") (pin "2") (pinfunction "2_2") (pintype "passive"))
      (node (ref "C7") (pin "2") (pinfunction "2_2") (pintype "passive"))
      (node (ref "C8") (pin "2") (pinfunction "2_2") (pintype "passive"))
      (node (ref "C9") (pin "2") (pinfunction "2_2") (pintype "passive"))
      (node (ref "D3") (pin "2") (pinfunction "GND_2") (pintype "bidirectional"))
      (node (ref "D4") (pin "1") (pinfunction "K_1") (pintype "bidirectional"))
      (node (ref "EPD_C1") (pin "1") (pinfunction "1_1") (pintype "passive"))
      (node (ref "EPD_C10") (pin "1") (pinfunction "1_1") (pintype "passive"))
      (node (ref "EPD_C11") (pin "1") (pinfunction "1_1") (pintype "passive"))
      (node (ref "EPD_C12") (pin "1") (pinfunction "1_1") (pintype "passive"))
      (node (ref "EPD_C2") (pin "1") (pinfunction "1_1") (pintype "passive"))
      (node (ref "EPD_C5") (pin "2") (pinfunction "2_2") (pintype "passive"))
      (node (ref "EPD_C6") (pin "1") (pinfunction "1_1") (pintype "passive"))
      (node (ref "EPD_C7") (pin "1") (pinfunction "1_1") (pintype "passive"))
      (node (ref "EPD_C8") (pin "1") (pinfunction "1_1") (pintype "passive"))
      (node (ref "EPD_C9") (pin "1") (pinfunction "1_1") (pintype "passive"))
      (node (ref "IC1") (pin "D2") (pinfunction "GND_D2") (pintype "bidirectional"))
      (node (ref "IC2") (pin "B1") (pinfunction "IN/TRIG_B1") (pintype "bidirectional"))
      (node (ref "IC2") (pin "B3") (pinfunction "GND_B3") (pintype "bidirectional"))
      (node (ref "IC3") (pin "8") (pinfunction "GNDIO_8") (pintype "bidirectional"))
      (node (ref "IC3") (pin "9") (pinfunction "GND_9") (pintype "bidirectional"))
      (node (ref "IC9") (pin "B1") (pinfunction "VSEL_B1") (pintype "bidirectional"))
      (node (ref "IC9") (pin "C1") (pinfunction "AGND_C1") (pintype "bidirectional"))
      (node (ref "IC9") (pin "C2") (pinfunction "PGND_1_C2") (pintype "bidirectional"))
      (node (ref "IC9") (pin "C3") (pinfunction "PGND_2_C3") (pintype "bidirectional"))
      (node (ref "J1") (pin "17") (pinfunction "17_17") (pintype "bidirectional"))
      (node (ref "J1") (pin "8") (pinfunction "8_8") (pintype "bidirectional"))
      (node (ref "J1") (pin "MP1") (pinfunction "MP1_MP1") (pintype "bidirectional"))
      (node (ref "J1") (pin "MP2") (pinfunction "MP2_MP2") (pintype "bidirectional"))
      (node (ref "J2") (pin "3") (pinfunction "3_3") (pintype "bidirectional"))
      (node (ref "J2") (pin "5") (pinfunction "5_5") (pintype "bidirectional"))
      (node (ref "J4") (pin "A12_B1") (pinfunction "GND_A12_B1") (pintype "power_in"))
      (node (ref "J4") (pin "A1_B12") (pinfunction "GND_A1_B12") (pintype "power_in"))
      (node (ref "J4") (pin "SH1") (pinfunction "SHIELD_SH1") (pintype "passive"))
      (node (ref "J4") (pin "SH2") (pinfunction "SHIELD_SH2") (pintype "passive"))
      (node (ref "J4") (pin "SH3") (pinfunction "SHIELD_SH3") (pintype "passive"))
      (node (ref "J4") (pin "SH4") (pinfunction "SHIELD_SH4") (pintype "passive"))
      (node (ref "R1_USB") (pin "1") (pinfunction "1_1") (pintype "bidirectional"))
      (node (ref "R2_EP_DR") (pin "1") (pinfunction "1_1") (pintype "bidirectional"))
      (node (ref "R2_USB") (pin "2") (pinfunction "2_2") (pintype "bidirectional"))
      (node (ref "R3") (pin "1") (pinfunction "1_1") (pintype "bidirectional"))
      (node (ref "R9") (pin "1") (pinfunction "1_1") (pintype "bidirectional"))
      (node (ref "R_TYPE_SEL") (pin "1") (pinfunction "1_1") (pintype "bidirectional"))
      (node (ref "SJ1") (pin "1") (pinfunction "1_1") (pintype "passive"))
      (node (ref "SW_DN") (pin "1") (pinfunction "1_1") (pintype "passive"))
      (node (ref "SW_ENT") (pin "1") (pinfunction "1_1") (pintype "passive"))
      (node (ref "SW_UP") (pin "1") (pinfunction "1_1") (pintype "passive"))
      (node (ref "TP_BAT_GND") (pin "TP") (pinfunction "TP_TP") (pintype "input"))
      (node (ref "TP_GND") (pin "TP") (pinfunction "TP_TP") (pintype "input"))
      (node (ref "U$3") (pin "2") (pinfunction "2_2") (pintype "passive"))
      (node (ref "U1") (pin "P$74") (pinfunction "VSS_PAD_P$74") (pintype "bidirectional"))
      (node (ref "U1") (pin "P$75") (pinfunction "VSS_PAD_P$75") (pintype "bidirectional"))
      (node (ref "U1") (pin "P$76") (pinfunction "VSS_PAD_P$76") (pintype "bidirectional"))
      (node (ref "U1") (pin "P$77") (pinfunction "VSS_PAD_P$77") (pintype "bidirectional"))
      (node (ref "U1") (pin "P$78") (pinfunction "VSS_PAD_P$78") (pintype "bidirectional"))
      (node (ref "U1") (pin "P$79") (pinfunction "VSS_PAD_P$79") (pintype "bidirectional"))
      (node (ref "U1") (pin "P$80") (pinfunction "VSS_PAD_P$80") (pintype "bidirectional"))
      (node (ref "U1") (pin "P$81") (pinfunction "VSS_PAD_P$81") (pintype "bidirectional"))
      (node (ref "U1") (pin "P$82") (pinfunction "VSS_PAD_P$82") (pintype "bidirectional"))
      (node (ref "U1") (pin "P$83") (pinfunction "VSS_PAD_P$83") (pintype "bidirectional"))
      (node (ref "U1") (pin "P$84") (pinfunction "VSS_PAD_P$84") (pintype "bidirectional"))
      (node (ref "U1") (pin "P$85") (pinfunction "VSS_PAD_P$85") (pintype "bidirectional"))
      (node (ref "U1") (pin "P$86") (pinfunction "VSS_PAD_P$86") (pintype "bidirectional"))
      (node (ref "U1") (pin "P$87") (pinfunction "VSS_PAD_P$87") (pintype "bidirectional"))
      (node (ref "U1") (pin "P$88") (pinfunction "VSS_PAD_P$88") (pintype "bidirectional"))
      (node (ref "U1") (pin "P$89") (pinfunction "VSS_PAD_P$89") (pintype "bidirectional"))
      (node (ref "U1") (pin "P$90") (pinfunction "VSS_PAD_P$90") (pintype "bidirectional"))
      (node (ref "U1") (pin "P$B7") (pinfunction "VSS_P$B7") (pintype "power_in"))
      (node (ref "U1") (pin "P$F23") (pinfunction "VSS_PA_P$F23") (pintype "bidirectional"))
      (node (ref "U3") (pin "1") (pinfunction "CTG_1") (pintype "power_in"))
      (node (ref "U3") (pin "4") (pinfunction "GND_4") (pintype "power_in"))
      (node (ref "U3") (pin "6") (pinfunction "QSTRT_6") (pintype "input"))
      (node (ref "U3") (pin "9") (pinfunction "EP_9") (pintype "power_in"))
      (node (ref "X1") (pin "2") (pinfunction "2_2") (pintype "passive"))
      (node (ref "X1") (pin "4") (pinfunction "4_4") (pintype "passive"))
    )
    (net (code "17") (name "HAPTIC_EN") (class "Default")
      (node (ref "IC2") (pin "A1") (pinfunction "EN_A1") (pintype "bidirectional"))
      (node (ref "U1") (pin "P$U1") (pinfunction "P0.12_P$U1") (pintype "bidirectional"))
    )
    (net (code "18") (name "IMU_INT1") (class "Default")
      (node (ref "IC3") (pin "5") (pinfunction "INT1_5") (pintype "bidirectional"))
      (node (ref "U1") (pin "P$N1") (pinfunction "P0.08_P$N1") (pintype "bidirectional"))
    )
    (net (code "19") (name "IMU_INT2") (class "Default")
      (node (ref "IC3") (pin "6") (pinfunction "INT2_6") (pintype "bidirectional"))
      (node (ref "U1") (pin "P$P2") (pinfunction "P1.08_P$P2") (pintype "bidirectional"))
    )
    (net (code "20") (name "LX1") (class "Default")
      (node (ref "IC9") (pin "B2") (pinfunction "SW1_1_B2") (pintype "bidirectional"))
      (node (ref "IC9") (pin "B3") (pinfunction "SW1_2_B3") (pintype "bidirectional"))
      (node (ref "L7") (pin "1") (pinfunction "1_1") (pintype "bidirectional"))
    )
    (net (code "21") (name "LX2") (class "Default")
      (node (ref "IC9") (pin "D2") (pinfunction "SW2_1_D2") (pintype "bidirectional"))
      (node (ref "IC9") (pin "D3") (pinfunction "SW2_2_D3") (pintype "bidirectional"))
      (node (ref "L7") (pin "2") (pinfunction "2_2") (pintype "bidirectional"))
    )
    (net (code "22") (name "MOSI") (class "Default")
      (node (ref "J1") (pin "14") (pinfunction "14_14") (pintype "bidirectional"))
      (node (ref "U1") (pin "P$B13") (pinfunction "P0.03/AIN1_P$B13") (pintype "bidirectional"))
    )
    (net (code "23") (name "Net-(D2-K)") (class "Default")
      (node (ref "C2-EP-DR") (pin "1") (pinfunction "1_1") (pintype "passive"))
      (node (ref "D2") (pin "1") (pinfunction "K_1") (pintype "bidirectional"))
      (node (ref "D4") (pin "2") (pinfunction "A_2") (pintype "bidirectional"))
    )
    (net (code "24") (name "Net-(D5-A)") (class "Default")
      (node (ref "C2-EP-DR") (pin "2") (pinfunction "2_2") (pintype "passive"))
      (node (ref "D5") (pin "2") (pinfunction "A_2") (pintype "bidirectional"))
      (node (ref "L5") (pin "1") (pinfunction "1_1") (pintype "passive"))
      (node (ref "Q3") (pin "3") (pinfunction "D_3") (pintype "bidirectional"))
    )
    (net (code "25") (name "Net-(EPD_C1-Pad2)") (class "Default")
      (node (ref "EPD_C1") (pin "2") (pinfunction "2_2") (pintype "passive"))
      (node (ref "J1") (pin "5") (pinfunction "5_5") (pintype "bidirectional"))
    )
    (net (code "26") (name "Net-(EPD_C2-Pad2)") (class "Default")
      (node (ref "EPD_C2") (pin "2") (pinfunction "2_2") (pintype "passive"))
      (node (ref "J1") (pin "4") (pinfunction "4_4") (pintype "bidirectional"))
    )
    (net (code "27") (name "Net-(EPD_C6-Pad2)") (class "Default")
      (node (ref "EPD_C6") (pin "2") (pinfunction "2_2") (pintype "passive"))
      (node (ref "J1") (pin "18") (pinfunction "18_18") (pintype "bidirectional"))
    )
    (net (code "28") (name "Net-(EPD_C7-Pad2)") (class "Default")
      (node (ref "EPD_C7") (pin "2") (pinfunction "2_2") (pintype "passive"))
      (node (ref "J1") (pin "19") (pinfunction "19_19") (pintype "bidirectional"))
    )
    (net (code "29") (name "Net-(EPD_C8-Pad2)") (class "Default")
      (node (ref "EPD_C8") (pin "2") (pinfunction "2_2") (pintype "passive"))
      (node (ref "J1") (pin "20") (pinfunction "20_20") (pintype "bidirectional"))
    )
    (net (code "30") (name "Net-(EPD_C10-Pad2)") (class "Default")
      (node (ref "EPD_C10") (pin "2") (pinfunction "2_2") (pintype "passive"))
      (node (ref "J1") (pin "22") (pinfunction "22_22") (pintype "bidirectional"))
    )
    (net (code "31") (name "Net-(EPD_C12-Pad2)") (class "Default")
      (node (ref "EPD_C12") (pin "2") (pinfunction "2_2") (pintype "passive"))
      (node (ref "J1") (pin "24") (pinfunction "24_24") (pintype "bidirectional"))
    )
    (net (code "32") (name "Net-(IC1-TS{slash}MR)") (class "Default")
      (node (ref "IC1") (pin "D1") (pinfunction "TS/MR_D1") (pintype "bidirectional"))
      (node (ref "R9") (pin "2") (pinfunction "2_2") (pintype "bidirectional"))
    )
    (net (code "33") (name "Net-(IC2-REG)") (class "Default")
      (node (ref "C32") (pin "2") (pinfunction "2_2") (pintype "passive"))
      (node (ref "IC2") (pin "A2") (pinfunction "REG_A2") (pintype "bidirectional"))
    )
    (net (code "34") (name "Net-(IC3-SDO)") (class "Default")
      (node (ref "IC3") (pin "1") (pinfunction "SDO_1") (pintype "bidirectional"))
      (node (ref "R3") (pin "2") (pinfunction "2_2") (pintype "bidirectional"))
    )
    (net (code "35") (name "Net-(IC9-SCL)") (class "Default")
      (node (ref "IC9") (pin "D1") (pinfunction "SCL_D1") (pintype "bidirectional"))
      (node (ref "R4") (pin "2") (pinfunction "2_2") (pintype "bidirectional"))
    )
    (net (code "36") (name "Net-(IC9-SDA)") (class "Default")
      (node (ref "IC9") (pin "E1") (pinfunction "SDA_E1") (pintype "bidirectional"))
      (node (ref "R2") (pin "2") (pinfunction "2_2") (pintype "bidirectional"))
    )
    (net (code "37") (name "Net-(J4-CC1)") (class "Default")
      (node (ref "J4") (pin "A5") (pinfunction "CC1_A5") (pintype "bidirectional"))
      (node (ref "R1_USB") (pin "2") (pinfunction "2_2") (pintype "bidirectional"))
    )
    (net (code "38") (name "Net-(J4-CC2)") (class "Default")
      (node (ref "J4") (pin "B5") (pinfunction "CC2_B5") (pintype "bidirectional"))
      (node (ref "R2_USB") (pin "1") (pinfunction "1_1") (pintype "bidirectional"))
    )
    (net (code "39") (name "Net-(L2-Pad2)") (class "Default")
      (node (ref "L2") (pin "2") (pinfunction "2_2") (pintype "passive"))
      (node (ref "L3") (pin "1") (pinfunction "1_1") (pintype "passive"))
    )
    (net (code "40") (name "Net-(R1_EP_DR-Pad1)") (class "Default")
      (node (ref "R1_EP_DR") (pin "1") (pinfunction "1_1") (pintype "bidirectional"))
      (node (ref "R_TYPE_SEL") (pin "2") (pinfunction "2_2") (pintype "bidirectional"))
      (node (ref "SJ1") (pin "2") (pinfunction "2_2") (pintype "passive"))
    )
    (net (code "41") (name "Net-(U1-ANT)") (class "Default")
      (node (ref "C3") (pin "1") (pinfunction "1_1") (pintype "passive"))
      (node (ref "L1") (pin "1") (pinfunction "1_1") (pintype "passive"))
      (node (ref "U1") (pin "P$H23") (pinfunction "ANT_P$H23") (pintype "bidirectional"))
    )
    (net (code "42") (name "Net-(U1-DCC)") (class "Default")
      (node (ref "L2") (pin "1") (pinfunction "1_1") (pintype "passive"))
      (node (ref "U1") (pin "P$B3") (pinfunction "DCC_P$B3") (pintype "output"))
    )
    (net (code "43") (name "Net-(U1-DEC2)") (class "Default")
      (node (ref "C13") (pin "1") (pinfunction "1_1") (pintype "passive"))
      (node (ref "U1") (pin "P$A18") (pinfunction "DEC2_P$A18") (pintype "bidirectional"))
    )
    (net (code "44") (name "Net-(U1-DEC3V3)") (class "Default")
      (node (ref "C20") (pin "1") (pinfunction "1_1") (pintype "passive"))
      (node (ref "U1") (pin "P$AC5") (pinfunction "DEC3V3_P$AC5") (pintype "bidirectional"))
    )
    (net (code "45") (name "Net-(U1-DEC5)") (class "Default")
      (node (ref "C9") (pin "1") (pinfunction "1_1") (pintype "passive"))
      (node (ref "U1") (pin "P$N24") (pinfunction "DEC5_P$N24") (pintype "bidirectional"))
    )
    (net (code "46") (name "Net-(U1-XC1)") (class "Default")
      (node (ref "C1") (pin "1") (pinfunction "1_1") (pintype "passive"))
      (node (ref "U1") (pin "P$B24") (pinfunction "XC1_P$B24") (pintype "input"))
      (node (ref "X1") (pin "1") (pinfunction "1_1") (pintype "passive"))
    )
    (net (code "47") (name "Net-(U1-XC2)") (class "Default")
      (node (ref "C2") (pin "1") (pinfunction "1_1") (pintype "passive"))
      (node (ref "U1") (pin "P$A23") (pinfunction "XC2_P$A23") (pintype "output"))
      (node (ref "X1") (pin "3") (pinfunction "3_3") (pintype "passive"))
    )
    (net (code "48") (name "OUT+") (class "Default")
      (node (ref "IC2") (pin "A3") (pinfunction "OUT+_A3") (pintype "bidirectional"))
      (node (ref "TP_OP") (pin "TP") (pinfunction "TP_TP") (pintype "input"))
    )
    (net (code "49") (name "OUT-") (class "Default")
      (node (ref "IC2") (pin "C3") (pinfunction "OUT-_C3") (pintype "bidirectional"))
      (node (ref "TP_ON") (pin "TP") (pinfunction "TP_TP") (pintype "input"))
    )
    (net (code "50") (name "P0.00{slash}XL1") (class "Default")
      (node (ref "C17") (pin "2") (pinfunction "2_2") (pintype "passive"))
      (node (ref "U1") (pin "P$D2") (pinfunction "P0.00/XL1_P$D2") (pintype "bidirectional"))
      (node (ref "X2") (pin "1") (pinfunction "1_1") (pintype "passive"))
    )
    (net (code "51") (name "P0.01{slash}XL2") (class "Default")
      (node (ref "C18") (pin "2") (pinfunction "2_2") (pintype "passive"))
      (node (ref "U1") (pin "P$F2") (pinfunction "P0.01/XL2_P$F2") (pintype "bidirectional"))
      (node (ref "X2") (pin "2") (pinfunction "2_2") (pintype "passive"))
    )
    (net (code "52") (name "P0.04") (class "Default")
      (node (ref "U1") (pin "P$J1") (pinfunction "P0.04/AIN2_P$J1") (pintype "bidirectional"))
    )
    (net (code "53") (name "P0.09") (class "Default")
      (node (ref "U1") (pin "P$L24") (pinfunction "P0.09/NFC1_P$L24") (pintype "bidirectional"))
    )
    (net (code "54") (name "P0.13") (class "Default")
      (node (ref "C30") (pin "2") (pinfunction "2_2") (pintype "passive"))
      (node (ref "R5") (pin "1") (pinfunction "1_1") (pintype "bidirectional"))
      (node (ref "SW_UP") (pin "2") (pinfunction "2_2") (pintype "passive"))
      (node (ref "U1") (pin "P$AD8") (pinfunction "P0.13_P$AD8") (pintype "bidirectional"))
    )
    (net (code "55") (name "P0.14") (class "Default")
      (node (ref "C31") (pin "2") (pinfunction "2_2") (pintype "passive"))
      (node (ref "R8") (pin "1") (pinfunction "1_1") (pintype "bidirectional"))
      (node (ref "SW_ENT") (pin "2") (pinfunction "2_2") (pintype "passive"))
      (node (ref "U1") (pin "P$AC9") (pinfunction "P0.14_P$AC9") (pintype "bidirectional"))
    )
    (net (code "56") (name "P0.19") (class "Default")
      (node (ref "U1") (pin "P$AC15") (pinfunction "P0.19_P$AC15") (pintype "bidirectional"))
    )
    (net (code "57") (name "P0.20") (class "Default")
      (node (ref "U1") (pin "P$AD16") (pinfunction "P0.20_P$AD16") (pintype "bidirectional"))
    )
    (net (code "58") (name "P0.21") (class "Default")
      (node (ref "U1") (pin "P$AC17") (pinfunction "P0.21_P$AC17") (pintype "bidirectional"))
    )
    (net (code "59") (name "P0.22") (class "Default")
      (node (ref "U1") (pin "P$AD18") (pinfunction "P0.22_P$AD18") (pintype "bidirectional"))
    )
    (net (code "60") (name "P0.23") (class "Default")
      (node (ref "U1") (pin "P$AC19") (pinfunction "P0.23_P$AC19") (pintype "bidirectional"))
    )
    (net (code "61") (name "P0.24") (class "Default")
      (node (ref "U1") (pin "P$AD20") (pinfunction "P0.24_P$AD20") (pintype "bidirectional"))
    )
    (net (code "62") (name "P0.25") (class "Default")
      (node (ref "U1") (pin "P$AC21") (pinfunction "P0.25_P$AC21") (pintype "bidirectional"))
    )
    (net (code "63") (name "P0.26") (class "Default")
      (node (ref "U1") (pin "P$G1") (pinfunction "P0.26_P$G1") (pintype "bidirectional"))
    )
    (net (code "64") (name "P0.27") (class "Default")
      (node (ref "U1") (pin "P$H2") (pinfunction "P0.27_P$H2") (pintype "bidirectional"))
    )
    (net (code "65") (name "P0.28") (class "Default")
      (node (ref "U1") (pin "P$B11") (pinfunction "P0.28/AIN4_P$B11") (pintype "bidirectional"))
    )
    (net (code "66") (name "P0.29") (class "Default")
      (node (ref "U1") (pin "P$A10") (pinfunction "P0.29/AIN5_P$A10") (pintype "bidirectional"))
    )
    (net (code "67") (name "P0.30") (class "Default")
      (node (ref "U1") (pin "P$B9") (pinfunction "P0.30/AIN6_P$B9") (pintype "bidirectional"))
    )
    (net (code "68") (name "P0.31") (class "Default")
      (node (ref "U1") (pin "P$A8") (pinfunction "P0.31/AIN7_P$A8") (pintype "bidirectional"))
    )
    (net (code "69") (name "P1.01") (class "Default")
      (node (ref "DMG2305UX-7") (pin "1") (pinfunction "G_1") (pintype "bidirectional"))
      (node (ref "R_PWR_EPD") (pin "1") (pinfunction "1_1") (pintype "bidirectional"))
      (node (ref "U1") (pin "P$Y23") (pinfunction "P1.01_P$Y23") (pintype "bidirectional"))
    )
    (net (code "70") (name "P1.02") (class "Default")
      (node (ref "C29") (pin "2") (pinfunction "2_2") (pintype "passive"))
      (node (ref "R7") (pin "1") (pinfunction "1_1") (pintype "bidirectional"))
      (node (ref "SW_DN") (pin "2") (pinfunction "2_2") (pintype "passive"))
      (node (ref "U1") (pin "P$W24") (pinfunction "P1.02_P$W24") (pintype "bidirectional"))
    )
    (net (code "71") (name "P1.03") (class "Default")
      (node (ref "U1") (pin "P$V23") (pinfunction "P1.03_P$V23") (pintype "bidirectional"))
    )
    (net (code "72") (name "P1.04") (class "Default")
      (node (ref "U1") (pin "P$U24") (pinfunction "P1.04_P$U24") (pintype "bidirectional"))
    )
    (net (code "73") (name "P1.05") (class "Default")
      (node (ref "U1") (pin "P$T23") (pinfunction "P1.05_P$T23") (pintype "bidirectional"))
    )
    (net (code "74") (name "P1.06") (class "Default")
      (node (ref "U1") (pin "P$R24") (pinfunction "P1.06_P$R24") (pintype "bidirectional"))
    )
    (net (code "75") (name "P1.07") (class "Default")
      (node (ref "U1") (pin "P$P23") (pinfunction "P1.07_P$P23") (pintype "bidirectional"))
    )
    (net (code "76") (name "P1.09") (class "Default")
      (node (ref "U1") (pin "P$R1") (pinfunction "P1.09_P$R1") (pintype "bidirectional"))
    )
    (net (code "77") (name "P1.10") (class "Default")
      (node (ref "U1") (pin "P$A20") (pinfunction "P1.10_P$A20") (pintype "bidirectional"))
    )
    (net (code "78") (name "P1.11") (class "Default")
      (node (ref "U1") (pin "P$B19") (pinfunction "P1.11_P$B19") (pintype "bidirectional"))
    )
    (net (code "79") (name "P1.12") (class "Default")
      (node (ref "U1") (pin "P$B17") (pinfunction "P1.12_P$B17") (pintype "bidirectional"))
    )
    (net (code "80") (name "P1.13") (class "Default")
      (node (ref "U1") (pin "P$A16") (pinfunction "P1.13_P$A16") (pintype "bidirectional"))
    )
    (net (code "81") (name "P1.14") (class "Default")
      (node (ref "U1") (pin "P$B15") (pinfunction "P1.14_P$B15") (pintype "bidirectional"))
    )
    (net (code "82") (name "P1.15") (class "Default")
      (node (ref "U1") (pin "P$A14") (pinfunction "P1.15_P$A14") (pintype "bidirectional"))
    )
    (net (code "83") (name "PMIC_INT") (class "Default")
      (node (ref "IC1") (pin "A1") (pinfunction "~{INT}_A1") (pintype "bidirectional"))
      (node (ref "U1") (pin "P$T2") (pinfunction "P0.11_P$T2") (pintype "bidirectional"))
    )
    (net (code "84") (name "PREVGH") (class "Default")
      (node (ref "D5") (pin "1") (pinfunction "K_1") (pintype "bidirectional"))
      (node (ref "EPD_C9") (pin "2") (pinfunction "2_2") (pintype "passive"))
      (node (ref "J1") (pin "21") (pinfunction "21_21") (pintype "bidirectional"))
    )
    (net (code "85") (name "PREVGL") (class "Default")
      (node (ref "D2") (pin "2") (pinfunction "A_2") (pintype "bidirectional"))
      (node (ref "EPD_C11") (pin "2") (pinfunction "2_2") (pintype "passive"))
      (node (ref "J1") (pin "23") (pinfunction "23_23") (pintype "bidirectional"))
    )
    (net (code "86") (name "RESE") (class "Default")
      (node (ref "J1") (pin "3") (pinfunction "3_3") (pintype "bidirectional"))
      (node (ref "Q3") (pin "2") (pinfunction "S_2") (pintype "bidirectional"))
      (node (ref "R1_EP_DR") (pin "2") (pinfunction "2_2") (pintype "bidirectional"))
    )
    (net (code "87") (name "RESET") (class "Default")
      (node (ref "J2") (pin "6") (pinfunction "6_6") (pintype "bidirectional"))
      (node (ref "TP_RESET") (pin "TP") (pinfunction "TP_TP") (pintype "input"))
      (node (ref "U1") (pin "P$AC13") (pinfunction "P0.18/RESET_P$AC13") (pintype "bidirectional"))
    )
    (net (code "88") (name "RF") (class "Default")
      (node (ref "ANT1") (pin "1") (pinfunction "FEED_1") (pintype "input"))
      (node (ref "C22") (pin "1") (pinfunction "1_1") (pintype "passive"))
      (node (ref "C4") (pin "1") (pinfunction "1_1") (pintype "passive"))
      (node (ref "L1") (pin "2") (pinfunction "2_2") (pintype "passive"))
    )
    (net (code "89") (name "SCK") (class "Default")
      (node (ref "J1") (pin "13") (pinfunction "13_13") (pintype "bidirectional"))
      (node (ref "U1") (pin "P$A12") (pinfunction "P0.02/AIN0_P$A12") (pintype "bidirectional"))
    )
    (net (code "90") (name "SCL") (class "Default")
      (node (ref "IC1") (pin "B1") (pinfunction "SCL_B1") (pintype "bidirectional"))
      (node (ref "IC2") (pin "C1") (pinfunction "SCL_C1") (pintype "bidirectional"))
      (node (ref "IC3") (pin "12") (pinfunction "SCX_12") (pintype "bidirectional"))
      (node (ref "R17") (pin "2") (pinfunction "2_2") (pintype "bidirectional"))
      (node (ref "R4") (pin "1") (pinfunction "1_1") (pintype "bidirectional"))
      (node (ref "TP_SCL") (pin "TP") (pinfunction "TP_TP") (pintype "input"))
      (node (ref "U1") (pin "P$M2") (pinfunction "P0.07_P$M2") (pintype "bidirectional"))
      (node (ref "U3") (pin "7") (pinfunction "SCL_7") (pintype "input"))
    )
    (net (code "91") (name "SDA") (class "Default")
      (node (ref "IC1") (pin "C1") (pinfunction "SDA_C1") (pintype "bidirectional"))
      (node (ref "IC2") (pin "B2") (pinfunction "SDA_B2") (pintype "bidirectional"))
      (node (ref "IC3") (pin "2") (pinfunction "SDX_2") (pintype "bidirectional"))
      (node (ref "R18") (pin "2") (pinfunction "2_2") (pintype "bidirectional"))
      (node (ref "R2") (pin "1") (pinfunction "1_1") (pintype "bidirectional"))
      (node (ref "TP_SDA") (pin "TP") (pinfunction "TP_TP") (pintype "input"))
      (node (ref "U1") (pin "P$L1") (pinfunction "P0.06_P$L1") (pintype "bidirectional"))
      (node (ref "U3") (pin "8") (pinfunction "SDA_8") (pintype "bidirectional"))
    )
    (net (code "92") (name "SWDCLK") (class "Default")
      (node (ref "J2") (pin "4") (pinfunction "4_4") (pintype "bidirectional"))
      (node (ref "TP_SWDCLK") (pin "TP") (pinfunction "TP_TP") (pintype "input"))
      (node (ref "U1") (pin "P$AA24") (pinfunction "SWDCLK_P$AA24") (pintype "input"))
    )
    (net (code "93") (name "SWDIO") (class "Default")
      (node (ref "J2") (pin "2") (pinfunction "2_2") (pintype "bidirectional"))
      (node (ref "TP_SWDIO") (pin "TP") (pinfunction "TP_TP") (pintype "input"))
      (node (ref "U1") (pin "P$AC24") (pinfunction "SWDIO_P$AC24") (pintype "bidirectional"))
    )
    (net (code "94") (name "SWO") (class "Default")
      (node (ref "TP_SWO") (pin "TP") (pinfunction "TP_TP") (pintype "input"))
      (node (ref "U1") (pin "P$AD22") (pinfunction "P1.00_P$AD22") (pintype "bidirectional"))
    )
    (net (code "95") (name "VBAT") (class "Default")
      (node (ref "C27") (pin "2") (pinfunction "2_2") (pintype "passive"))
      (node (ref "C37") (pin "2") (pinfunction "2_2") (pintype "passive"))
      (node (ref "IC1") (pin "C2") (pinfunction "BAT_C2") (pintype "bidirectional"))
      (node (ref "TP_VBAT") (pin "TP") (pinfunction "TP_TP") (pintype "input"))
      (node (ref "U3") (pin "2") (pinfunction "CELL_2") (pintype "power_in"))
      (node (ref "U3") (pin "3") (pinfunction "VDD_3") (pintype "power_in"))
    )
    (net (code "96") (name "VBUS") (class "Default")
      (node (ref "C21") (pin "1") (pinfunction "1_1") (pintype "passive"))
      (node (ref "C38") (pin "2") (pinfunction "2_2") (pintype "passive"))
      (node (ref "C42") (pin "1") (pinfunction "1_1") (pintype "passive"))
      (node (ref "C43") (pin "1") (pinfunction "1_1") (pintype "passive"))
      (node (ref "D3") (pin "5") (pinfunction "VBUS_5") (pintype "bidirectional"))
      (node (ref "IC1") (pin "A2") (pinfunction "IN_A2") (pintype "bidirectional"))
      (node (ref "J4") (pin "A4_B9") (pinfunction "VBUS_A4_B9") (pintype "power_in"))
      (node (ref "J4") (pin "A9_B4") (pinfunction "VBUS_A9_B4") (pintype "power_in"))
      (node (ref "U1") (pin "P$AD2") (pinfunction "VBUS_P$AD2") (pintype "power_in"))
    )
    (net (code "97") (name "VREG") (class "Default")
      (node (ref "C23") (pin "2") (pinfunction "2_2") (pintype "passive"))
      (node (ref "C24") (pin "2") (pinfunction "2_2") (pintype "passive"))
      (node (ref "C39") (pin "1") (pinfunction "1_1") (pintype "passive"))
      (node (ref "IC1") (pin "B2") (pinfunction "SYS_B2") (pintype "bidirectional"))
      (node (ref "IC9") (pin "A1") (pinfunction "EN_A1") (pintype "bidirectional"))
      (node (ref "IC9") (pin "A2") (pinfunction "VIN_1_A2") (pintype "bidirectional"))
      (node (ref "IC9") (pin "A3") (pinfunction "VIN_2_A3") (pintype "bidirectional"))
      (node (ref "TP_VREG") (pin "TP") (pinfunction "TP_TP") (pintype "input"))
      (node (ref "U$3") (pin "1") (pinfunction "1_1") (pintype "passive"))
    )
    (net (code "98") (name "unconnected-(ANT1-NC-Pad2)") (class "Default")
      (node (ref "ANT1") (pin "2") (pinfunction "NC_2") (pintype "no_connect"))
    )
    (net (code "99") (name "unconnected-(IC3-ASCL-Pad11)") (class "Default")
      (node (ref "IC3") (pin "11") (pinfunction "ASCL_11") (pintype "bidirectional"))
    )
    (net (code "100") (name "unconnected-(IC3-ASDA-Pad4)") (class "Default")
      (node (ref "IC3") (pin "4") (pinfunction "ASDA_4") (pintype "bidirectional"))
    )
    (net (code "101") (name "unconnected-(J1-Pad1)") (class "Default")
      (node (ref "J1") (pin "1") (pinfunction "1_1") (pintype "bidirectional"))
    )
    (net (code "102") (name "unconnected-(J1-Pad6)") (class "Default")
      (node (ref "J1") (pin "6") (pinfunction "6_6") (pintype "bidirectional"))
    )
    (net (code "103") (name "unconnected-(J1-Pad7)") (class "Default")
      (node (ref "J1") (pin "7") (pinfunction "7_7") (pintype "bidirectional"))
    )
    (net (code "104") (name "unconnected-(J4-SBU1-PadA8)") (class "Default")
      (node (ref "J4") (pin "A8") (pinfunction "SBU1_A8") (pintype "bidirectional"))
    )
    (net (code "105") (name "unconnected-(J4-SBU2-PadB8)") (class "Default")
      (node (ref "J4") (pin "B8") (pinfunction "SBU2_B8") (pintype "bidirectional"))
    )
    (net (code "106") (name "unconnected-(U1-DCCH-PadP$AB2)") (class "Default")
      (node (ref "U1") (pin "P$AB2") (pinfunction "DCCH_P$AB2") (pintype "bidirectional"))
    )
  )
)
